# DACAmplification.net
KiCad netlist of a schematic drawn in Altium Designer
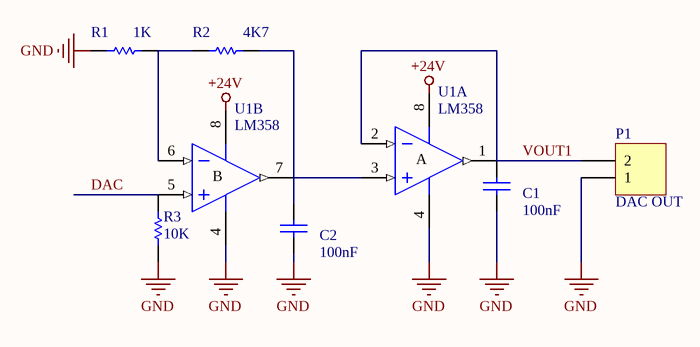
[diagram p0: DACAmplification.SchDoc]

(export (version "E")
  (design (tool "Eeschema 10.0.6"))
  (components
    (comp (ref "C1")
      (value "100nF")
      (footprint "C-0805")
      (description "Capacitor")
      (fields (field (name "Comment") "104") (field (name "PUBLISHER") "Altium Limited"))
      (libsource (lib "Miscellaneous Devices") (part "Cap"))
    )
    (comp (ref "C2")
      (value "100nF")
      (footprint "C-0805")
      (description "Capacitor")
      (fields (field (name "Comment") "104") (field (name "PUBLISHER") "Altium Limited"))
      (libsource (lib "Miscellaneous Devices") (part "Cap"))
    )
    (comp (ref "P1")
      (value "DAC OUT")
      (footprint "TER-KF128-2P")
      (description "Header, 2-Pin")
      (fields (field (name "Comment") "KF128-2P"))
      (libsource (lib "Miscellaneous Connectors") (part "Header 2"))
    )
    (comp (ref "R1")
      (value "1K")
      (footprint "R-0805")
      (description "Resistor")
      (fields (field (name "PUBLISHER") "Altium Limited"))
      (libsource (lib "Miscellaneous Devices") (part "Res1"))
    )
    (comp (ref "R2")
      (value "4K7")
      (footprint "R-0805")
      (description "Resistor")
      (fields (field (name "PUBLISHER") "Altium Limited"))
      (libsource (lib "Miscellaneous Devices") (part "Res1"))
    )
    (comp (ref "R3")
      (value "10K")
      (footprint "R-0805")
      (description "Resistor")
      (fields (field (name "PUBLISHER") "Altium Limited"))
      (libsource (lib "Miscellaneous Devices") (part "Res1"))
    )
    (comp (ref "U1")
      (value "LM358")
      (footprint "SK-DIP8-300")
      (description "JFET-Input Operational Amplifier")
      (fields (field (name "PUBLISHER") "Altium Limited"))
      (libsource (lib "TI Operational Amplifier") (part "TL082D"))
    )
  )
  (nets
    (net (code "1") (name "+24V") (class "Default")
      (node (ref "U1") (pin "8") (pinfunction "V+_8") (pintype "power_in"))
    )
    (net (code "2") (name "/DAC") (class "Default")
      (node (ref "R3") (pin "2") (pinfunction "2_2") (pintype "passive"))
      (node (ref "U1") (pin "5") (pinfunction "IN+_5") (pintype "input"))
    )
    (net (code "3") (name "/VOUT1") (class "Default")
      (node (ref "C1") (pin "2") (pinfunction "2_2") (pintype "passive"))
      (node (ref "P1") (pin "2") (pinfunction "2_2") (pintype "passive"))
      (node (ref "U1") (pin "1") (pinfunction "OUT_1") (pintype "output"))
      (node (ref "U1") (pin "2") (pinfunction "IN-_2") (pintype "input"))
    )
    (net (code "4") (name "GND") (class "Default")
      (node (ref "C1") (pin "1") (pinfunction "1_1") (pintype "passive"))
      (node (ref "C2") (pin "1") (pinfunction "1_1") (pintype "passive"))
      (node (ref "P1") (pin "1") (pinfunction "1_1") (pintype "passive"))
      (node (ref "R1") (pin "1") (pinfunction "1_1") (pintype "passive"))
      (node (ref "R3") (pin "1") (pinfunction "1_1") (pintype "passive"))
      (node (ref "U1") (pin "4") (pinfunction "V-_4") (pintype "power_in"))
    )
    (net (code "5") (name "Net-(U1A-IN+)") (class "Default")
      (node (ref "C2") (pin "2") (pinfunction "2_2") (pintype "passive"))
      (node (ref "R2") (pin "2") (pinfunction "2_2") (pintype "passive"))
      (node (ref "U1") (pin "3") (pinfunction "IN+_3") (pintype "input"))
      (node (ref "U1") (pin "7") (pinfunction "OUT_7") (pintype "output"))
    )
    (net (code "6") (name "Net-(U1B-IN-)") (class "Default")
      (node (ref "R1") (pin "2") (pinfunction "2_2") (pintype "passive"))
      (node (ref "R2") (pin "1") (pinfunction "1_1") (pintype "passive"))
      (node (ref "U1") (pin "6") (pinfunction "IN-_6") (pintype "input"))
    )
  )
)
